# ESP8266_Programmer.net
KiCad netlist of a schematic drawn in EAGLE
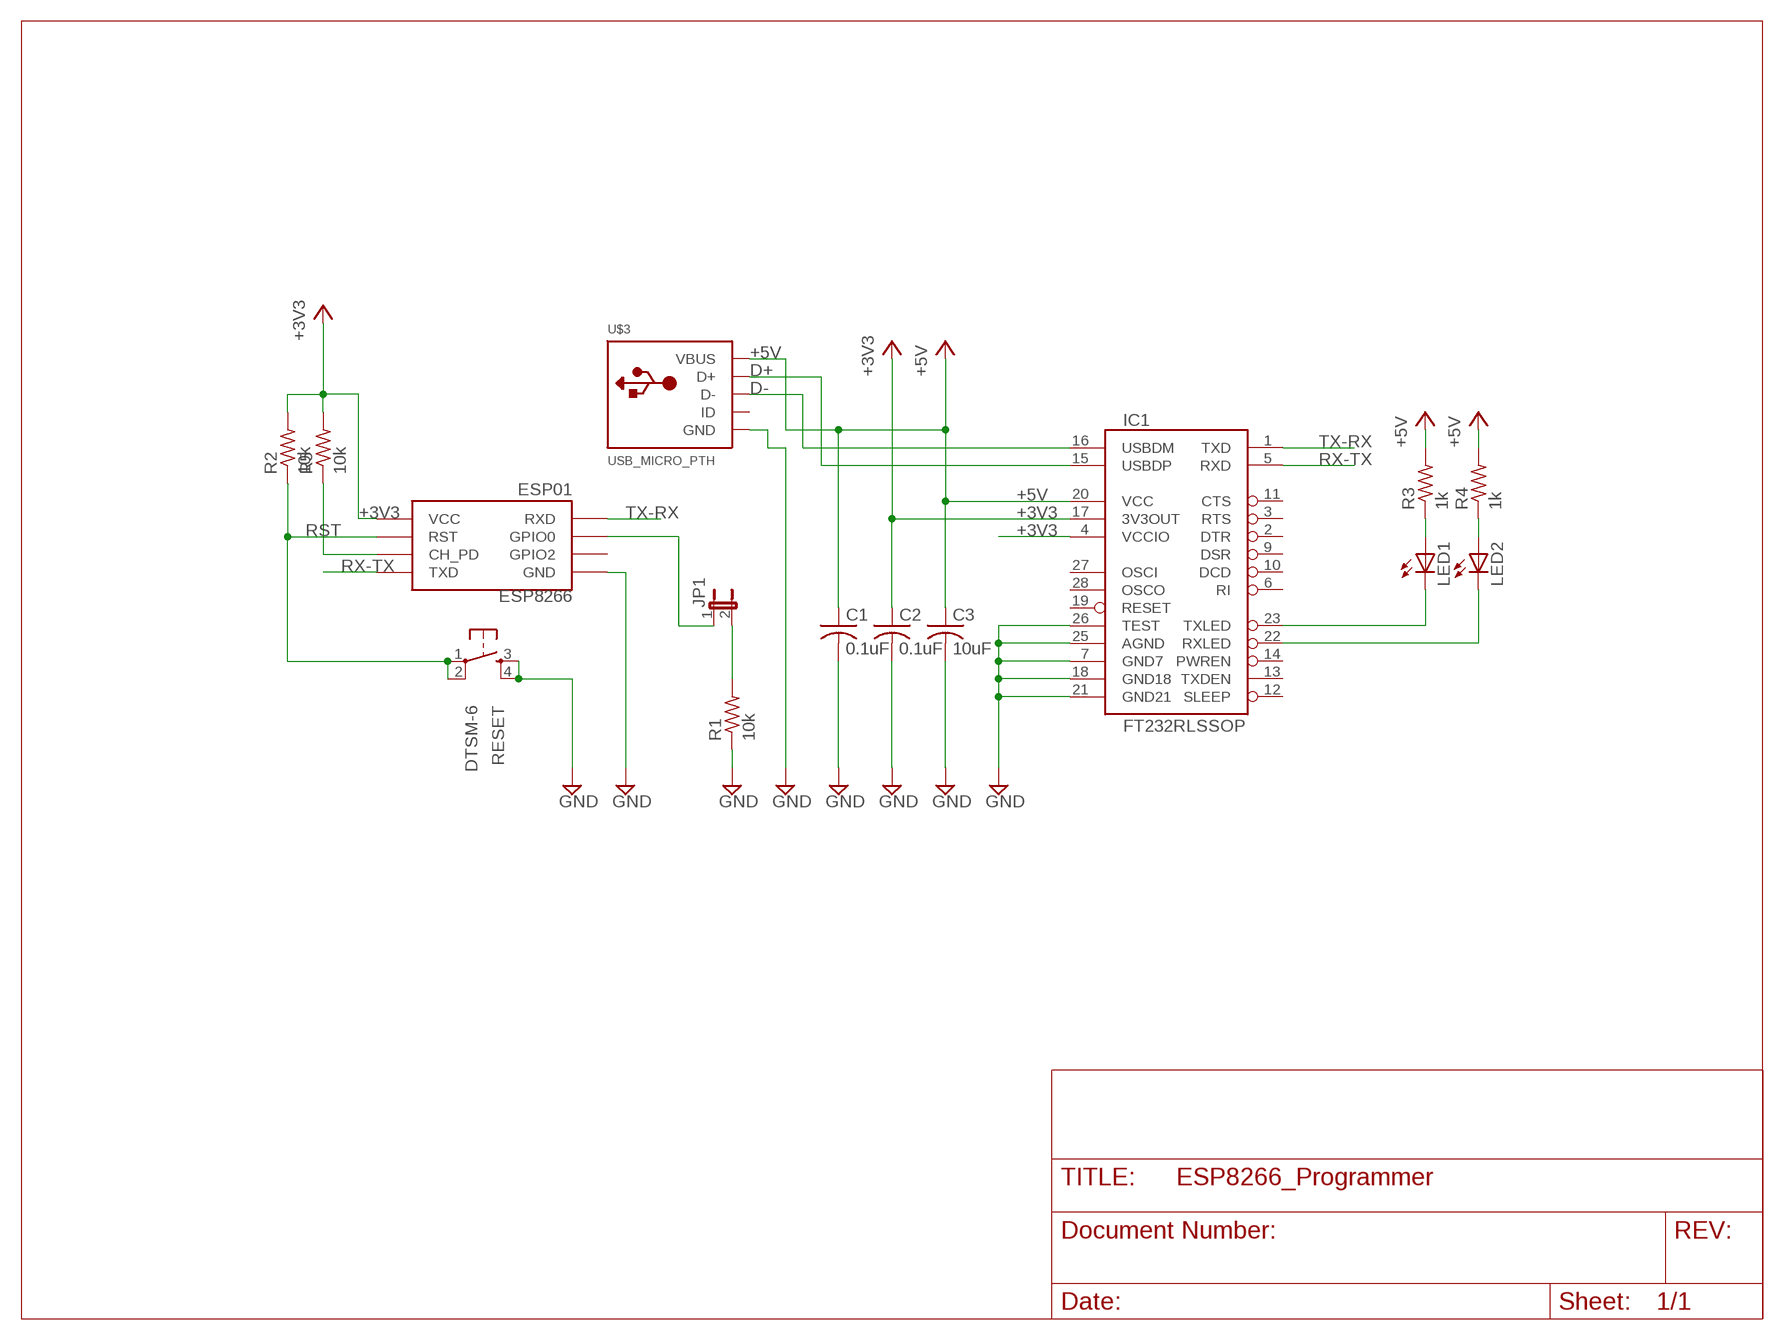
[diagram p0: schematic, sheet 1]

(export (version "E")
  (design (tool "Eeschema 10.0.6"))
  (components
    (comp (ref "C1")
      (value "0.1uF")
      (footprint "eagle-import:C0603")
      (libsource (lib "eagle-import") (part "C-USC0603"))
    )
    (comp (ref "C2")
      (value "0.1uF")
      (footprint "eagle-import:C0603")
      (libsource (lib "eagle-import") (part "C-USC0603"))
    )
    (comp (ref "C3")
      (value "10uF")
      (footprint "eagle-import:C1206")
      (libsource (lib "eagle-import") (part "C-USC1206"))
    )
    (comp (ref "ESP8266")
      (value "ESP01")
      (footprint "eagle-import:ESP01")
      (libsource (lib "eagle-import") (part "ESP01"))
    )
    (comp (ref "IC1")
      (value "FT232RLSSOP")
      (footprint "eagle-import:SSOP28DB")
      (libsource (lib "eagle-import") (part "FT232RLSSOP"))
    )
    (comp (ref "JP1")
      (value "JUMPER-2PTH")
      (footprint "eagle-import:1X02")
      (libsource (lib "eagle-import") (part "JUMPER-2PTH"))
    )
    (comp (ref "LED1")
      (value "LEDCHIP-LED0603")
      (footprint "eagle-import:CHIP-LED0603")
      (libsource (lib "eagle-import") (part "LEDCHIP-LED0603"))
    )
    (comp (ref "LED2")
      (value "LEDCHIP-LED0603")
      (footprint "eagle-import:CHIP-LED0603")
      (libsource (lib "eagle-import") (part "LEDCHIP-LED0603"))
    )
    (comp (ref "R1")
      (value "10k")
      (footprint "eagle-import:R0603")
      (libsource (lib "eagle-import") (part "R-US_R0603"))
    )
    (comp (ref "R2")
      (value "10k")
      (footprint "eagle-import:R0603")
      (libsource (lib "eagle-import") (part "R-US_R0603"))
    )
    (comp (ref "R3")
      (value "1k")
      (footprint "eagle-import:R0603")
      (libsource (lib "eagle-import") (part "R-US_R0603"))
    )
    (comp (ref "R4")
      (value "1k")
      (footprint "eagle-import:R0603")
      (libsource (lib "eagle-import") (part "R-US_R0603"))
    )
    (comp (ref "R5")
      (value "10k")
      (footprint "eagle-import:R0603")
      (libsource (lib "eagle-import") (part "R-US_R0603"))
    )
    (comp (ref "RESET")
      (value "DTSM-6")
      (footprint "eagle-import:DTSM-6")
      (libsource (lib "eagle-import") (part "DTSM-6"))
    )
    (comp (ref "U$3")
      (value "USB_MICRO_PTH")
      (footprint "eagle-import:USB_MICRO_PTH")
      (libsource (lib "eagle-import") (part "USB_MICRO_PTH"))
    )
  )
  (nets
    (net (code "1") (name "+3V3") (class "Default")
      (node (ref "C2") (pin "1") (pinfunction "1_1") (pintype "passive"))
      (node (ref "ESP8266") (pin "VCC") (pinfunction "VCC_VCC") (pintype "bidirectional"))
      (node (ref "IC1") (pin "17") (pinfunction "3V3OUT_17") (pintype "output"))
      (node (ref "IC1") (pin "4") (pinfunction "VCCIO_4") (pintype "power_in"))
      (node (ref "R2") (pin "2") (pinfunction "2_2") (pintype "passive"))
      (node (ref "R5") (pin "2") (pinfunction "2_2") (pintype "passive"))
    )
    (net (code "2") (name "+5V") (class "Default")
      (node (ref "C1") (pin "1") (pinfunction "1_1") (pintype "passive"))
      (node (ref "C3") (pin "1") (pinfunction "1_1") (pintype "passive"))
      (node (ref "IC1") (pin "20") (pinfunction "VCC_20") (pintype "power_in"))
      (node (ref "R3") (pin "2") (pinfunction "2_2") (pintype "passive"))
      (node (ref "R4") (pin "2") (pinfunction "2_2") (pintype "passive"))
      (node (ref "U$3") (pin "1") (pinfunction "VBUS_1") (pintype "power_in"))
    )
    (net (code "3") (name "/D+") (class "Default")
      (node (ref "IC1") (pin "15") (pinfunction "USBDP_15") (pintype "bidirectional"))
      (node (ref "U$3") (pin "3") (pinfunction "D+_3") (pintype "bidirectional"))
    )
    (net (code "4") (name "/D-") (class "Default")
      (node (ref "IC1") (pin "16") (pinfunction "USBDM_16") (pintype "bidirectional"))
      (node (ref "U$3") (pin "2") (pinfunction "D-_2") (pintype "bidirectional"))
    )
    (net (code "5") (name "/RST") (class "Default")
      (node (ref "ESP8266") (pin "RST") (pinfunction "RST_RST") (pintype "bidirectional"))
      (node (ref "R2") (pin "1") (pinfunction "1_1") (pintype "passive"))
      (node (ref "RESET") (pin "1") (pinfunction "1_1") (pintype "passive"))
      (node (ref "RESET") (pin "2") (pinfunction "2_2") (pintype "passive"))
    )
    (net (code "6") (name "/RX-TX") (class "Default")
      (node (ref "ESP8266") (pin "TX") (pinfunction "TXD_TX") (pintype "bidirectional"))
      (node (ref "IC1") (pin "5") (pinfunction "RXD_5") (pintype "input"))
    )
    (net (code "7") (name "/TX-RX") (class "Default")
      (node (ref "ESP8266") (pin "RX") (pinfunction "RXD_RX") (pintype "bidirectional"))
      (node (ref "IC1") (pin "1") (pinfunction "TXD_1") (pintype "output"))
    )
    (net (code "8") (name "GND") (class "Default")
      (node (ref "C1") (pin "2") (pinfunction "2_2") (pintype "passive"))
      (node (ref "C2") (pin "2") (pinfunction "2_2") (pintype "passive"))
      (node (ref "C3") (pin "2") (pinfunction "2_2") (pintype "passive"))
      (node (ref "ESP8266") (pin "GND") (pinfunction "GND_GND") (pintype "bidirectional"))
      (node (ref "IC1") (pin "18") (pinfunction "GND18_18") (pintype "power_in"))
      (node (ref "IC1") (pin "21") (pinfunction "GND21_21") (pintype "power_in"))
      (node (ref "IC1") (pin "25") (pinfunction "AGND_25") (pintype "power_in"))
      (node (ref "IC1") (pin "26") (pinfunction "TEST_26") (pintype "input"))
      (node (ref "IC1") (pin "7") (pinfunction "GND7_7") (pintype "power_in"))
      (node (ref "R1") (pin "1") (pinfunction "1_1") (pintype "passive"))
      (node (ref "RESET") (pin "3") (pinfunction "3_3") (pintype "passive"))
      (node (ref "RESET") (pin "4") (pinfunction "4_4") (pintype "passive"))
      (node (ref "U$3") (pin "5") (pinfunction "GND_5") (pintype "power_in"))
    )
    (net (code "9") (name "Net-(ESP8266-PadCH_PD)") (class "Default")
      (node (ref "ESP8266") (pin "CH_PD") (pinfunction "CH_PD_CH_PD") (pintype "bidirectional"))
      (node (ref "R5") (pin "1") (pinfunction "1_1") (pintype "passive"))
    )
    (net (code "10") (name "Net-(ESP8266-PadGPIO0)") (class "Default")
      (node (ref "ESP8266") (pin "GPIO0") (pinfunction "GPIO0_GPIO0") (pintype "bidirectional"))
      (node (ref "JP1") (pin "1") (pinfunction "1_1") (pintype "passive"))
    )
    (net (code "11") (name "Net-(IC1-RXLED)") (class "Default")
      (node (ref "IC1") (pin "22") (pinfunction "RXLED_22") (pintype "input"))
      (node (ref "LED2") (pin "C") (pinfunction "C_C") (pintype "passive"))
    )
    (net (code "12") (name "Net-(IC1-TXLED)") (class "Default")
      (node (ref "IC1") (pin "23") (pinfunction "TXLED_23") (pintype "input"))
      (node (ref "LED1") (pin "C") (pinfunction "C_C") (pintype "passive"))
    )
    (net (code "13") (name "Net-(JP1-Pad2)") (class "Default")
      (node (ref "JP1") (pin "2") (pinfunction "2_2") (pintype "passive"))
      (node (ref "R1") (pin "2") (pinfunction "2_2") (pintype "passive"))
    )
    (net (code "14") (name "Net-(LED1-PadA)") (class "Default")
      (node (ref "LED1") (pin "A") (pinfunction "A_A") (pintype "passive"))
      (node (ref "R3") (pin "1") (pinfunction "1_1") (pintype "passive"))
    )
    (net (code "15") (name "Net-(LED2-PadA)") (class "Default")
      (node (ref "LED2") (pin "A") (pinfunction "A_A") (pintype "passive"))
      (node (ref "R4") (pin "1") (pinfunction "1_1") (pintype "passive"))
    )
    (net (code "16") (name "unconnected-(ESP8266-PadGPIO2)") (class "Default")
      (node (ref "ESP8266") (pin "GPIO2") (pinfunction "GPIO2_GPIO2") (pintype "bidirectional"))
    )
    (net (code "17") (name "unconnected-(IC1-CTS-Pad11)") (class "Default")
      (node (ref "IC1") (pin "11") (pinfunction "CTS_11") (pintype "input"))
    )
    (net (code "18") (name "unconnected-(IC1-DCD-Pad10)") (class "Default")
      (node (ref "IC1") (pin "10") (pinfunction "DCD_10") (pintype "input"))
    )
    (net (code "19") (name "unconnected-(IC1-DSR-Pad9)") (class "Default")
      (node (ref "IC1") (pin "9") (pinfunction "DSR_9") (pintype "input"))
    )
    (net (code "20") (name "unconnected-(IC1-DTR-Pad2)") (class "Default")
      (node (ref "IC1") (pin "2") (pinfunction "DTR_2") (pintype "output"))
    )
    (net (code "21") (name "unconnected-(IC1-OSCI-Pad27)") (class "Default")
      (node (ref "IC1") (pin "27") (pinfunction "OSCI_27") (pintype "input"))
    )
    (net (code "22") (name "unconnected-(IC1-OSCO-Pad28)") (class "Default")
      (node (ref "IC1") (pin "28") (pinfunction "OSCO_28") (pintype "output"))
    )
    (net (code "23") (name "unconnected-(IC1-PWREN-Pad14)") (class "Default")
      (node (ref "IC1") (pin "14") (pinfunction "PWREN_14") (pintype "input"))
    )
    (net (code "24") (name "unconnected-(IC1-RESET-Pad19)") (class "Default")
      (node (ref "IC1") (pin "19") (pinfunction "RESET_19") (pintype "input"))
    )
    (net (code "25") (name "unconnected-(IC1-RI-Pad6)") (class "Default")
      (node (ref "IC1") (pin "6") (pinfunction "RI_6") (pintype "input"))
    )
    (net (code "26") (name "unconnected-(IC1-RTS-Pad3)") (class "Default")
      (node (ref "IC1") (pin "3") (pinfunction "RTS_3") (pintype "output"))
    )
    (net (code "27") (name "unconnected-(IC1-SLEEP-Pad12)") (class "Default")
      (node (ref "IC1") (pin "12") (pinfunction "SLEEP_12") (pintype "input"))
    )
    (net (code "28") (name "unconnected-(IC1-TXDEN-Pad13)") (class "Default")
      (node (ref "IC1") (pin "13") (pinfunction "TXDEN_13") (pintype "input"))
    )
    (net (code "29") (name "unconnected-(U$3-ID-Pad4)") (class "Default")
      (node (ref "U$3") (pin "4") (pinfunction "ID_4") (pintype "bidirectional"))
    )
  )
)
